# small_pcb_explorator_58mm_lyre_v1_1.net
KiCad netlist of a schematic drawn in EAGLE
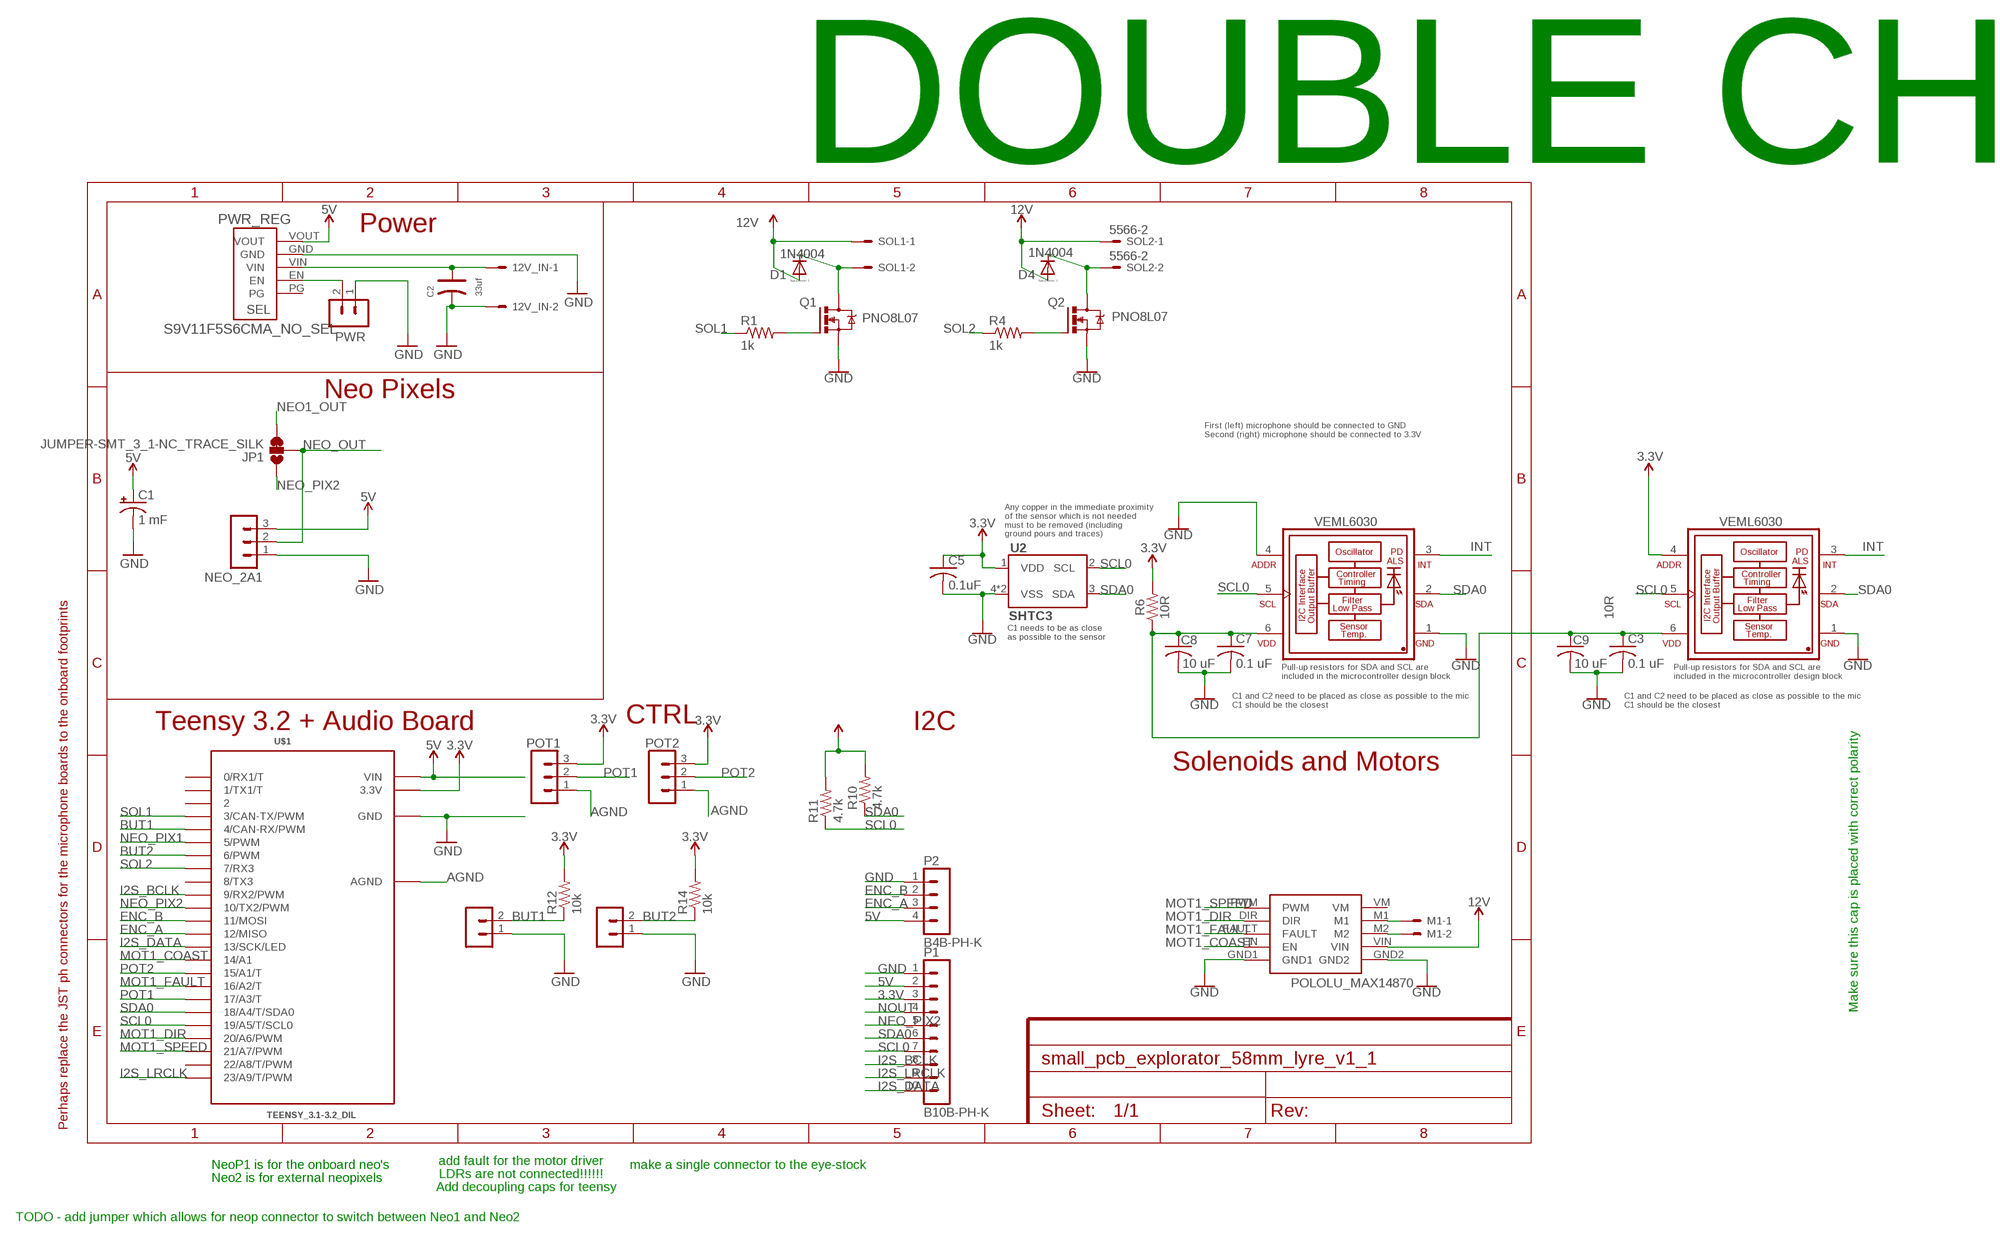
[diagram p0: schematic, sheet 1, part 1 of 2]
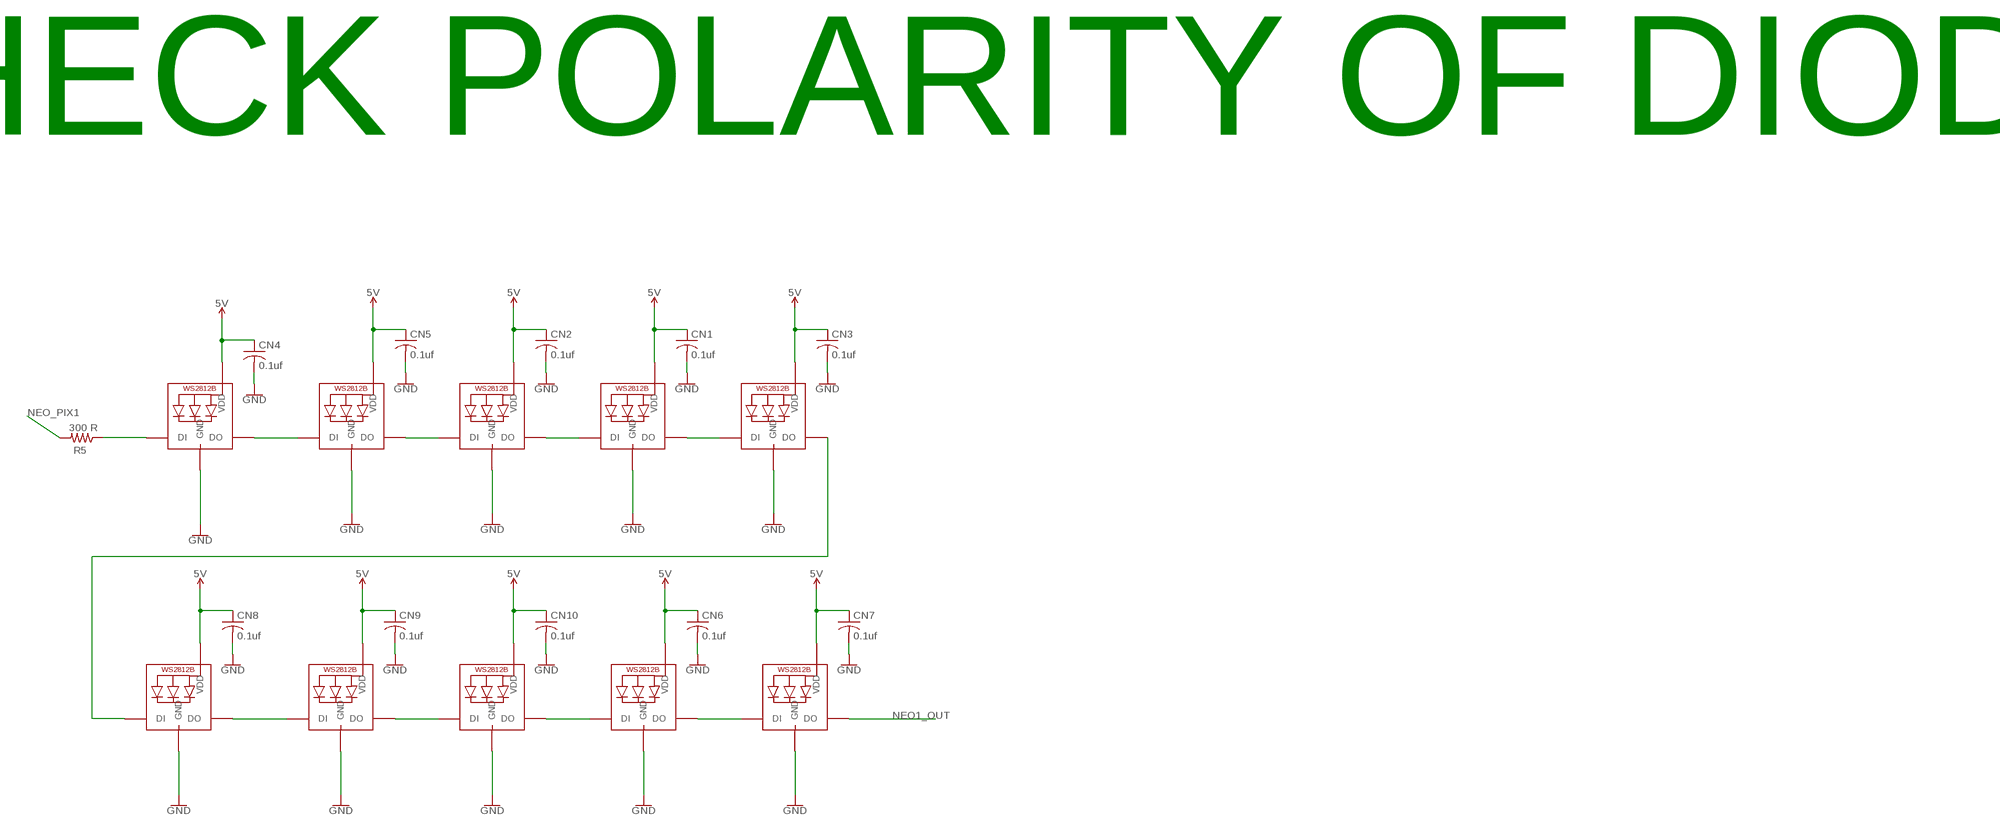
[diagram p1: schematic, sheet 1, part 2 of 2]

(export (version "E")
  (design (tool "Eeschema 10.0.6"))
  (components
    (comp (ref "12V_IN")
      (value "5566-2")
      (footprint "eagle-import:5566-2")
      (fields (field (name "MF") "MOLEX"))
      (libsource (lib "eagle-import") (part "5566-2"))
    )
    (comp (ref "BUT1")
      (value "B2B-PH-K")
      (footprint "eagle-import:B2B-PH-K")
      (libsource (lib "eagle-import") (part "B2B-PH-K"))
    )
    (comp (ref "BUT2")
      (value "B2B-PH-K")
      (footprint "eagle-import:B2B-PH-K")
      (libsource (lib "eagle-import") (part "B2B-PH-K"))
    )
    (comp (ref "C1")
      (value "1 mF")
      (footprint "eagle-import:UD-10X10_NICHICON")
      (libsource (lib "eagle-import") (part "CPOL-USUD-10X10"))
    )
    (comp (ref "C2")
      (value "33uf")
      (footprint "eagle-import:PC-D5.3MM")
      (fields (field (name "MPN") "KS 100uF/16V"))
      (libsource (lib "eagle-import") (part "DIP-ALUMINUM-47UF-16V(D5-H7MM)"))
    )
    (comp (ref "C3")
      (value "0.1 uF")
      (footprint "eagle-import:C0805")
      (libsource (lib "eagle-import") (part "C-USC0805"))
    )
    (comp (ref "C5")
      (value "0.1uF")
      (footprint "eagle-import:C0805")
      (libsource (lib "eagle-import") (part "C-USC0805"))
    )
    (comp (ref "C7")
      (value "0.1 uF")
      (footprint "eagle-import:C0805")
      (libsource (lib "eagle-import") (part "C-USC0805"))
    )
    (comp (ref "C8")
      (value "10 uF")
      (footprint "eagle-import:C0805")
      (libsource (lib "eagle-import") (part "C-USC0805"))
    )
    (comp (ref "C9")
      (value "10 uF")
      (footprint "eagle-import:C0805")
      (libsource (lib "eagle-import") (part "C-USC0805"))
    )
    (comp (ref "CN1")
      (value "0.1uf")
      (footprint "eagle-import:C0805K")
      (libsource (lib "eagle-import") (part "resistor_348_C-USC0805K"))
    )
    (comp (ref "CN2")
      (value "0.1uf")
      (footprint "eagle-import:C0805K")
      (libsource (lib "eagle-import") (part "resistor_348_C-USC0805K"))
    )
    (comp (ref "CN3")
      (value "0.1uf")
      (footprint "eagle-import:C0805K")
      (libsource (lib "eagle-import") (part "resistor_348_C-USC0805K"))
    )
    (comp (ref "CN4")
      (value "0.1uf")
      (footprint "eagle-import:C0805K")
      (libsource (lib "eagle-import") (part "resistor_348_C-USC0805K"))
    )
    (comp (ref "CN5")
      (value "0.1uf")
      (footprint "eagle-import:C0805K")
      (libsource (lib "eagle-import") (part "resistor_348_C-USC0805K"))
    )
    (comp (ref "CN6")
      (value "0.1uf")
      (footprint "eagle-import:C0805K")
      (libsource (lib "eagle-import") (part "resistor_348_C-USC0805K"))
    )
    (comp (ref "CN7")
      (value "0.1uf")
      (footprint "eagle-import:C0805K")
      (libsource (lib "eagle-import") (part "resistor_348_C-USC0805K"))
    )
    (comp (ref "CN8")
      (value "0.1uf")
      (footprint "eagle-import:C0805K")
      (libsource (lib "eagle-import") (part "resistor_348_C-USC0805K"))
    )
    (comp (ref "CN9")
      (value "0.1uf")
      (footprint "eagle-import:C0805K")
      (libsource (lib "eagle-import") (part "resistor_348_C-USC0805K"))
    )
    (comp (ref "CN10")
      (value "0.1uf")
      (footprint "eagle-import:C0805K")
      (libsource (lib "eagle-import") (part "resistor_348_C-USC0805K"))
    )
    (comp (ref "D1")
      (value "1N4004")
      (footprint "eagle-import:DIODE_DO35-7")
      (libsource (lib "eagle-import") (part "DIODE_E-DO35-7"))
    )
    (comp (ref "D4")
      (value "1N4004")
      (footprint "eagle-import:DIODE_DO35-7")
      (libsource (lib "eagle-import") (part "DIODE_E-DO35-7"))
    )
    (comp (ref "JP1")
      (value "JUMPER-SMT_3_1-NC_TRACE_SILK")
      (footprint "eagle-import:SMT-JUMPER_3_1-NC_TRACE_SILK")
      (libsource (lib "eagle-import") (part "JUMPER-SMT_3_1-NC_TRACE_SILK"))
    )
    (comp (ref "M1")
      (value "5566-2")
      (footprint "eagle-import:5566-2")
      (fields (field (name "MF") "MOLEX"))
      (libsource (lib "eagle-import") (part "5566-2"))
    )
    (comp (ref "MOT1")
      (value "POLOLU_MAX14870")
      (footprint "eagle-import:POLOLU_MAX14870")
      (libsource (lib "eagle-import") (part "POLOLU_MAX14870"))
    )
    (comp (ref "NEO1")
      (value "WS2812B5050")
      (footprint "eagle-import:WS2812B")
      (libsource (lib "eagle-import") (part "WS2812B5050"))
    )
    (comp (ref "NEO2")
      (value "WS2812B5050")
      (footprint "eagle-import:WS2812B")
      (libsource (lib "eagle-import") (part "WS2812B5050"))
    )
    (comp (ref "NEO3")
      (value "WS2812B5050")
      (footprint "eagle-import:WS2812B")
      (libsource (lib "eagle-import") (part "WS2812B5050"))
    )
    (comp (ref "NEO4")
      (value "WS2812B5050")
      (footprint "eagle-import:WS2812B")
      (libsource (lib "eagle-import") (part "WS2812B5050"))
    )
    (comp (ref "NEO5")
      (value "WS2812B5050")
      (footprint "eagle-import:WS2812B")
      (libsource (lib "eagle-import") (part "WS2812B5050"))
    )
    (comp (ref "NEO6")
      (value "WS2812B5050")
      (footprint "eagle-import:WS2812B")
      (libsource (lib "eagle-import") (part "WS2812B5050"))
    )
    (comp (ref "NEO7")
      (value "WS2812B5050")
      (footprint "eagle-import:WS2812B")
      (libsource (lib "eagle-import") (part "WS2812B5050"))
    )
    (comp (ref "NEO8")
      (value "WS2812B5050")
      (footprint "eagle-import:WS2812B")
      (libsource (lib "eagle-import") (part "WS2812B5050"))
    )
    (comp (ref "NEO9")
      (value "WS2812B5050")
      (footprint "eagle-import:WS2812B")
      (libsource (lib "eagle-import") (part "WS2812B5050"))
    )
    (comp (ref "NEO10")
      (value "WS2812B5050")
      (footprint "eagle-import:WS2812B")
      (libsource (lib "eagle-import") (part "WS2812B5050"))
    )
    (comp (ref "NEO_2A1")
      (value "B3B-PH-K")
      (footprint "eagle-import:B3B-PH-K")
      (libsource (lib "eagle-import") (part "B3B-PH-K"))
    )
    (comp (ref "P1")
      (value "B10B-PH-K")
      (footprint "eagle-import:B10B-PH-K")
      (libsource (lib "eagle-import") (part "B10B-PH-K"))
    )
    (comp (ref "P2")
      (value "B4B-PH-K")
      (footprint "eagle-import:B4B-PH-K")
      (libsource (lib "eagle-import") (part "B4B-PH-K"))
    )
    (comp (ref "POT1")
      (value "B3B-PH-K")
      (footprint "eagle-import:B3B-PH-K")
      (libsource (lib "eagle-import") (part "B3B-PH-K"))
    )
    (comp (ref "POT2")
      (value "B3B-PH-K")
      (footprint "eagle-import:B3B-PH-K")
      (libsource (lib "eagle-import") (part "B3B-PH-K"))
    )
    (comp (ref "PWR")
      (value "B2B-PH-K")
      (footprint "eagle-import:B2B-PH-K")
      (libsource (lib "eagle-import") (part "B2B-PH-K"))
    )
    (comp (ref "PWR_REG")
      (value "S9V11F5S6CMA_NO_SEL")
      (footprint "eagle-import:S9V11F3S5CMA_NO_SEL")
      (libsource (lib "eagle-import") (part "S9V11F5S6CMA_NO_SEL"))
    )
    (comp (ref "Q1")
      (value "PNO8L07")
      (footprint "eagle-import:TO220BV")
      (libsource (lib "eagle-import") (part "IRF540"))
    )
    (comp (ref "Q2")
      (value "PNO8L07")
      (footprint "eagle-import:TO220BV")
      (libsource (lib "eagle-import") (part "IRF540"))
    )
    (comp (ref "R1")
      (value "1k")
      (footprint "eagle-import:R0805")
      (libsource (lib "eagle-import") (part "rcl_334_R-US_R0805"))
    )
    (comp (ref "R4")
      (value "1k")
      (footprint "eagle-import:R0805")
      (libsource (lib "eagle-import") (part "rcl_334_R-US_R0805"))
    )
    (comp (ref "R5")
      (value "300 R")
      (footprint "eagle-import:R0805")
      (libsource (lib "eagle-import") (part "R-US_R0805"))
    )
    (comp (ref "R6")
      (value "10 R")
      (footprint "eagle-import:R0805")
      (libsource (lib "eagle-import") (part "R-US_R0805"))
    )
    (comp (ref "R10")
      (value "4.7k")
      (footprint "eagle-import:R0805")
      (libsource (lib "eagle-import") (part "rcl_334_R-US_R0805"))
    )
    (comp (ref "R11")
      (value "4.7k")
      (footprint "eagle-import:R0805")
      (libsource (lib "eagle-import") (part "rcl_334_R-US_R0805"))
    )
    (comp (ref "R12")
      (value "10k")
      (footprint "eagle-import:R0805")
      (libsource (lib "eagle-import") (part "rcl_334_R-US_R0805"))
    )
    (comp (ref "R14")
      (value "10k")
      (footprint "eagle-import:R0805")
      (libsource (lib "eagle-import") (part "rcl_334_R-US_R0805"))
    )
    (comp (ref "SOL1")
      (value "5566-2")
      (footprint "eagle-import:5566-2")
      (fields (field (name "MF") "MOLEX"))
      (libsource (lib "eagle-import") (part "5566-2"))
    )
    (comp (ref "SOL2")
      (value "5566-2")
      (footprint "eagle-import:5566-2")
      (fields (field (name "MF") "MOLEX"))
      (libsource (lib "eagle-import") (part "5566-2"))
    )
    (comp (ref "U$1")
      (value "TEENSY_3.1-3.2_DIL")
      (footprint "eagle-import:TEENSY_3.0-3.2&LC_DIL")
      (libsource (lib "eagle-import") (part "TEENSY_3.1-3.2_DIL"))
    )
    (comp (ref "U2")
      (value "SHTC3")
      (footprint "eagle-import:SHTC3")
      (libsource (lib "eagle-import") (part "SHTC3"))
    )
    (comp (ref "VMEL1")
      (value "VEML6030")
      (footprint "eagle-import:VISHAY_VEML6030_2X2X0.87")
      (fields (field (name "MF") "Vishay Semiconductor") (field (name "MP") "VEML6030-GS15"))
      (libsource (lib "eagle-import") (part "VEML6030-GS15"))
    )
    (comp (ref "VMEL2")
      (value "VEML6030")
      (footprint "eagle-import:VISHAY_VEML6030_2X2X0.87")
      (fields (field (name "MF") "Vishay Semiconductor") (field (name "MP") "VEML6030-GS15"))
      (libsource (lib "eagle-import") (part "VEML6030-GS15"))
    )
  )
  (nets
    (net (code "1") (name "/AGND") (class "Default")
      (node (ref "POT1") (pin "1") (pinfunction "1_1") (pintype "passive"))
      (node (ref "POT2") (pin "1") (pinfunction "1_1") (pintype "passive"))
      (node (ref "U$1") (pin "AGND") (pinfunction "AGND_AGND") (pintype "power_in"))
    )
    (net (code "2") (name "/BUT1") (class "Default")
      (node (ref "BUT1") (pin "2") (pinfunction "2_2") (pintype "passive"))
      (node (ref "R12") (pin "1") (pinfunction "1_1") (pintype "passive"))
      (node (ref "U$1") (pin "4") (pinfunction "4/CAN-RX/PWM_4") (pintype "bidirectional"))
    )
    (net (code "3") (name "/BUT2") (class "Default")
      (node (ref "BUT2") (pin "2") (pinfunction "2_2") (pintype "passive"))
      (node (ref "R14") (pin "1") (pinfunction "1_1") (pintype "passive"))
      (node (ref "U$1") (pin "6") (pinfunction "6/PWM_6") (pintype "bidirectional"))
    )
    (net (code "4") (name "/ENC_A") (class "Default")
      (node (ref "P2") (pin "3") (pinfunction "3_3") (pintype "passive"))
      (node (ref "U$1") (pin "12") (pinfunction "12/MISO_12") (pintype "bidirectional"))
    )
    (net (code "5") (name "/ENC_B") (class "Default")
      (node (ref "P2") (pin "2") (pinfunction "2_2") (pintype "passive"))
      (node (ref "U$1") (pin "11") (pinfunction "11/MOSI_11") (pintype "bidirectional"))
    )
    (net (code "6") (name "/I2S_BCLK") (class "Default")
      (node (ref "P1") (pin "8") (pinfunction "8_8") (pintype "passive"))
      (node (ref "U$1") (pin "9") (pinfunction "9/RX2/PWM_9") (pintype "bidirectional"))
    )
    (net (code "7") (name "/I2S_DATA") (class "Default")
      (node (ref "P1") (pin "10") (pinfunction "10_10") (pintype "passive"))
      (node (ref "U$1") (pin "13") (pinfunction "13/SCK/LED_13") (pintype "bidirectional"))
    )
    (net (code "8") (name "/I2S_LRCLK") (class "Default")
      (node (ref "P1") (pin "9") (pinfunction "9_9") (pintype "passive"))
      (node (ref "U$1") (pin "23/A9") (pinfunction "23/A9/T/PWM_23/A9") (pintype "bidirectional"))
    )
    (net (code "9") (name "/INT") (class "Default")
      (node (ref "VMEL1") (pin "3") (pinfunction "INT_3") (pintype "output"))
      (node (ref "VMEL2") (pin "3") (pinfunction "INT_3") (pintype "output"))
    )
    (net (code "10") (name "/MOT1_COAST") (class "Default")
      (node (ref "MOT1") (pin "EN") (pinfunction "EN_EN") (pintype "bidirectional"))
      (node (ref "U$1") (pin "14/A0") (pinfunction "14/A1_14/A0") (pintype "bidirectional"))
    )
    (net (code "11") (name "/MOT1_DIR") (class "Default")
      (node (ref "MOT1") (pin "DIR") (pinfunction "DIR_DIR") (pintype "bidirectional"))
      (node (ref "U$1") (pin "20/A6") (pinfunction "20/A6/PWM_20/A6") (pintype "bidirectional"))
    )
    (net (code "12") (name "/MOT1_FAULT") (class "Default")
      (node (ref "MOT1") (pin "FAULT") (pinfunction "FAULT_FAULT") (pintype "bidirectional"))
      (node (ref "U$1") (pin "16/A2") (pinfunction "16/A2/T_16/A2") (pintype "bidirectional"))
    )
    (net (code "13") (name "/MOT1_SPEED") (class "Default")
      (node (ref "MOT1") (pin "PWM") (pinfunction "PWM_PWM") (pintype "bidirectional"))
      (node (ref "U$1") (pin "21/A7") (pinfunction "21/A7/PWM_21/A7") (pintype "bidirectional"))
    )
    (net (code "14") (name "/NEO1_OUT") (class "Default")
      (node (ref "JP1") (pin "3") (pinfunction "3_3") (pintype "passive"))
      (node (ref "NEO7") (pin "2-DOUT") (pinfunction "DO_2-DOUT") (pintype "output"))
    )
    (net (code "15") (name "/NEO_OUT") (class "Default")
      (node (ref "JP1") (pin "2") (pinfunction "2_2") (pintype "passive"))
      (node (ref "NEO_2A1") (pin "2") (pinfunction "2_2") (pintype "passive"))
    )
    (net (code "16") (name "/NEO_PIX1") (class "Default")
      (node (ref "R5") (pin "2") (pinfunction "2_2") (pintype "passive"))
      (node (ref "U$1") (pin "5") (pinfunction "5/PWM_5") (pintype "bidirectional"))
    )
    (net (code "17") (name "/NEO_PIX2") (class "Default")
      (node (ref "JP1") (pin "1") (pinfunction "1_1") (pintype "passive"))
      (node (ref "P1") (pin "5") (pinfunction "5_5") (pintype "passive"))
      (node (ref "U$1") (pin "10") (pinfunction "10/TX2/PWM_10") (pintype "bidirectional"))
    )
    (net (code "18") (name "/NOUT") (class "Default")
      (node (ref "P1") (pin "4") (pinfunction "4_4") (pintype "passive"))
    )
    (net (code "19") (name "/POT1") (class "Default")
      (node (ref "POT1") (pin "2") (pinfunction "2_2") (pintype "passive"))
      (node (ref "U$1") (pin "17/A3") (pinfunction "17/A3/T_17/A3") (pintype "bidirectional"))
    )
    (net (code "20") (name "/POT2") (class "Default")
      (node (ref "POT2") (pin "2") (pinfunction "2_2") (pintype "passive"))
      (node (ref "U$1") (pin "15/A1") (pinfunction "15/A1/T_15/A1") (pintype "bidirectional"))
    )
    (net (code "21") (name "/SCL0") (class "Default")
      (node (ref "P1") (pin "7") (pinfunction "7_7") (pintype "passive"))
      (node (ref "R11") (pin "1") (pinfunction "1_1") (pintype "passive"))
      (node (ref "U$1") (pin "19/A5") (pinfunction "19/A5/T/SCL0_19/A5") (pintype "bidirectional"))
      (node (ref "U2") (pin "2") (pinfunction "SCL_2") (pintype "bidirectional"))
      (node (ref "VMEL1") (pin "5") (pinfunction "SCL_5") (pintype "input"))
      (node (ref "VMEL2") (pin "5") (pinfunction "SCL_5") (pintype "input"))
    )
    (net (code "22") (name "/SDA0") (class "Default")
      (node (ref "P1") (pin "6") (pinfunction "6_6") (pintype "passive"))
      (node (ref "R10") (pin "1") (pinfunction "1_1") (pintype "passive"))
      (node (ref "U$1") (pin "18/A4") (pinfunction "18/A4/T/SDA0_18/A4") (pintype "bidirectional"))
      (node (ref "U2") (pin "3") (pinfunction "SDA_3") (pintype "bidirectional"))
      (node (ref "VMEL1") (pin "2") (pinfunction "SDA_2") (pintype "bidirectional"))
      (node (ref "VMEL2") (pin "2") (pinfunction "SDA_2") (pintype "bidirectional"))
    )
    (net (code "23") (name "/SOL1") (class "Default")
      (node (ref "R1") (pin "1") (pinfunction "1_1") (pintype "passive"))
      (node (ref "U$1") (pin "3") (pinfunction "3/CAN-TX/PWM_3") (pintype "bidirectional"))
    )
    (net (code "24") (name "/SOL2") (class "Default")
      (node (ref "R4") (pin "1") (pinfunction "1_1") (pintype "passive"))
      (node (ref "U$1") (pin "7") (pinfunction "7/RX3_7") (pintype "bidirectional"))
    )
    (net (code "25") (name "3.3V") (class "Default")
      (node (ref "C5") (pin "1") (pinfunction "1_1") (pintype "passive"))
      (node (ref "P1") (pin "3") (pinfunction "3_3") (pintype "passive"))
      (node (ref "POT1") (pin "3") (pinfunction "3_3") (pintype "passive"))
      (node (ref "POT2") (pin "3") (pinfunction "3_3") (pintype "passive"))
      (node (ref "R10") (pin "2") (pinfunction "2_2") (pintype "passive"))
      (node (ref "R11") (pin "2") (pinfunction "2_2") (pintype "passive"))
      (node (ref "R12") (pin "2") (pinfunction "2_2") (pintype "passive"))
      (node (ref "R14") (pin "2") (pinfunction "2_2") (pintype "passive"))
      (node (ref "R6") (pin "2") (pinfunction "2_2") (pintype "passive"))
      (node (ref "U$1") (pin "3.3V") (pinfunction "3.3V_3.3V") (pintype "power_in"))
      (node (ref "U2") (pin "1") (pinfunction "VDD_1") (pintype "bidirectional"))
      (node (ref "VMEL2") (pin "4") (pinfunction "ADDR_4") (pintype "bidirectional"))
    )
    (net (code "26") (name "5V") (class "Default")
      (node (ref "C1") (pin "+") (pinfunction "+_+") (pintype "passive"))
      (node (ref "CN1") (pin "1") (pinfunction "1_1") (pintype "passive"))
      (node (ref "CN10") (pin "1") (pinfunction "1_1") (pintype "passive"))
      (node (ref "CN2") (pin "1") (pinfunction "1_1") (pintype "passive"))
      (node (ref "CN3") (pin "1") (pinfunction "1_1") (pintype "passive"))
      (node (ref "CN4") (pin "1") (pinfunction "1_1") (pintype "passive"))
      (node (ref "CN5") (pin "1") (pinfunction "1_1") (pintype "passive"))
      (node (ref "CN6") (pin "1") (pinfunction "1_1") (pintype "passive"))
      (node (ref "CN7") (pin "1") (pinfunction "1_1") (pintype "passive"))
      (node (ref "CN8") (pin "1") (pinfunction "1_1") (pintype "passive"))
      (node (ref "CN9") (pin "1") (pinfunction "1_1") (pintype "passive"))
      (node (ref "NEO1") (pin "1-VDD") (pinfunction "VDD_1-VDD") (pintype "power_in"))
      (node (ref "NEO10") (pin "1-VDD") (pinfunction "VDD_1-VDD") (pintype "power_in"))
      (node (ref "NEO2") (pin "1-VDD") (pinfunction "VDD_1-VDD") (pintype "power_in"))
      (node (ref "NEO3") (pin "1-VDD") (pinfunction "VDD_1-VDD") (pintype "power_in"))
      (node (ref "NEO4") (pin "1-VDD") (pinfunction "VDD_1-VDD") (pintype "power_in"))
      (node (ref "NEO5") (pin "1-VDD") (pinfunction "VDD_1-VDD") (pintype "power_in"))
      (node (ref "NEO6") (pin "1-VDD") (pinfunction "VDD_1-VDD") (pintype "power_in"))
      (node (ref "NEO7") (pin "1-VDD") (pinfunction "VDD_1-VDD") (pintype "power_in"))
      (node (ref "NEO8") (pin "1-VDD") (pinfunction "VDD_1-VDD") (pintype "power_in"))
      (node (ref "NEO9") (pin "1-VDD") (pinfunction "VDD_1-VDD") (pintype "power_in"))
      (node (ref "NEO_2A1") (pin "3") (pinfunction "3_3") (pintype "passive"))
      (node (ref "P1") (pin "2") (pinfunction "2_2") (pintype "passive"))
      (node (ref "P2") (pin "4") (pinfunction "4_4") (pintype "passive"))
      (node (ref "PWR_REG") (pin "VOUT") (pinfunction "VOUT_VOUT") (pintype "bidirectional"))
      (node (ref "U$1") (pin "VIN") (pinfunction "VIN_VIN") (pintype "power_in"))
    )
    (net (code "27") (name "12V") (class "Default")
      (node (ref "12V_IN") (pin "1") (pinfunction "S_1") (pintype "passive"))
      (node (ref "C2") (pin "+") (pinfunction "+_+") (pintype "passive"))
      (node (ref "D1") (pin "A") (pinfunction "C_A") (pintype "passive"))
      (node (ref "D4") (pin "A") (pinfunction "C_A") (pintype "passive"))
      (node (ref "MOT1") (pin "VIN") (pinfunction "VIN_VIN") (pintype "bidirectional"))
      (node (ref "PWR_REG") (pin "VIN") (pinfunction "VIN_VIN") (pintype "bidirectional"))
      (node (ref "SOL1") (pin "1") (pinfunction "S_1") (pintype "passive"))
      (node (ref "SOL2") (pin "1") (pinfunction "S_1") (pintype "passive"))
    )
    (net (code "28") (name "GND") (class "Default")
      (node (ref "12V_IN") (pin "2") (pinfunction "S_2") (pintype "passive"))
      (node (ref "BUT1") (pin "1") (pinfunction "1_1") (pintype "passive"))
      (node (ref "BUT2") (pin "1") (pinfunction "1_1") (pintype "passive"))
      (node (ref "C1") (pin "-") (pinfunction "-_-") (pintype "passive"))
      (node (ref "C2") (pin "-") (pinfunction "-_-") (pintype "passive"))
      (node (ref "C3") (pin "2") (pinfunction "2_2") (pintype "passive"))
      (node (ref "C5") (pin "2") (pinfunction "2_2") (pintype "passive"))
      (node (ref "C7") (pin "2") (pinfunction "2_2") (pintype "passive"))
      (node (ref "C8") (pin "2") (pinfunction "2_2") (pintype "passive"))
      (node (ref "C9") (pin "2") (pinfunction "2_2") (pintype "passive"))
      (node (ref "CN1") (pin "2") (pinfunction "2_2") (pintype "passive"))
      (node (ref "CN10") (pin "2") (pinfunction "2_2") (pintype "passive"))
      (node (ref "CN2") (pin "2") (pinfunction "2_2") (pintype "passive"))
      (node (ref "CN3") (pin "2") (pinfunction "2_2") (pintype "passive"))
      (node (ref "CN4") (pin "2") (pinfunction "2_2") (pintype "passive"))
      (node (ref "CN5") (pin "2") (pinfunction "2_2") (pintype "passive"))
      (node (ref "CN6") (pin "2") (pinfunction "2_2") (pintype "passive"))
      (node (ref "CN7") (pin "2") (pinfunction "2_2") (pintype "passive"))
      (node (ref "CN8") (pin "2") (pinfunction "2_2") (pintype "passive"))
      (node (ref "CN9") (pin "2") (pinfunction "2_2") (pintype "passive"))
      (node (ref "MOT1") (pin "GND1") (pinfunction "GND1_GND1") (pintype "bidirectional"))
      (node (ref "MOT1") (pin "GND2") (pinfunction "GND2_GND2") (pintype "bidirectional"))
      (node (ref "NEO1") (pin "3-GND") (pinfunction "GND_3-GND") (pintype "power_in"))
      (node (ref "NEO10") (pin "3-GND") (pinfunction "GND_3-GND") (pintype "power_in"))
      (node (ref "NEO2") (pin "3-GND") (pinfunction "GND_3-GND") (pintype "power_in"))
      (node (ref "NEO3") (pin "3-GND") (pinfunction "GND_3-GND") (pintype "power_in"))
      (node (ref "NEO4") (pin "3-GND") (pinfunction "GND_3-GND") (pintype "power_in"))
      (node (ref "NEO5") (pin "3-GND") (pinfunction "GND_3-GND") (pintype "power_in"))
      (node (ref "NEO6") (pin "3-GND") (pinfunction "GND_3-GND") (pintype "power_in"))
      (node (ref "NEO7") (pin "3-GND") (pinfunction "GND_3-GND") (pintype "power_in"))
      (node (ref "NEO8") (pin "3-GND") (pinfunction "GND_3-GND") (pintype "power_in"))
      (node (ref "NEO9") (pin "3-GND") (pinfunction "GND_3-GND") (pintype "power_in"))
      (node (ref "NEO_2A1") (pin "1") (pinfunction "1_1") (pintype "passive"))
      (node (ref "P1") (pin "1") (pinfunction "1_1") (pintype "passive"))
      (node (ref "P2") (pin "1") (pinfunction "1_1") (pintype "passive"))
      (node (ref "PWR") (pin "1") (pinfunction "1_1") (pintype "passive"))
      (node (ref "PWR_REG") (pin "GND") (pinfunction "GND_GND") (pintype "bidirectional"))
      (node (ref "Q1") (pin "S") (pinfunction "S_S") (pintype "passive"))
      (node (ref "Q2") (pin "S") (pinfunction "S_S") (pintype "passive"))
      (node (ref "U$1") (pin "GND") (pinfunction "GND_GND") (pintype "power_in"))
      (node (ref "U2") (pin "4") (pinfunction "VSS_4") (pintype "bidirectional"))
      (node (ref "U2") (pin "5") (pinfunction "VSS_5") (pintype "bidirectional"))
      (node (ref "VMEL1") (pin "1") (pinfunction "GND_1") (pintype "power_in"))
      (node (ref "VMEL1") (pin "4") (pinfunction "ADDR_4") (pintype "bidirectional"))
      (node (ref "VMEL2") (pin "1") (pinfunction "GND_1") (pintype "power_in"))
    )
    (net (code "29") (name "Net-(D1-A)") (class "Default")
      (node (ref "D1") (pin "C") (pinfunction "A_C") (pintype "passive"))
      (node (ref "Q1") (pin "D") (pinfunction "D_D") (pintype "passive"))
      (node (ref "SOL1") (pin "2") (pinfunction "S_2") (pintype "passive"))
    )
    (net (code "30") (name "Net-(D4-A)") (class "Default")
      (node (ref "D4") (pin "C") (pinfunction "A_C") (pintype "passive"))
      (node (ref "Q2") (pin "D") (pinfunction "D_D") (pintype "passive"))
      (node (ref "SOL2") (pin "2") (pinfunction "S_2") (pintype "passive"))
    )
    (net (code "31") (name "Net-(M1A-S)") (class "Default")
      (node (ref "M1") (pin "1") (pinfunction "S_1") (pintype "passive"))
      (node (ref "MOT1") (pin "M1") (pinfunction "M1_M1") (pintype "bidirectional"))
    )
    (net (code "32") (name "Net-(M1B-S)") (class "Default")
      (node (ref "M1") (pin "2") (pinfunction "S_2") (pintype "passive"))
      (node (ref "MOT1") (pin "M2") (pinfunction "M2_M2") (pintype "bidirectional"))
    )
    (net (code "33") (name "Net-(NEO1-DI)") (class "Default")
      (node (ref "NEO1") (pin "4-DIN") (pinfunction "DI_4-DIN") (pintype "input"))
      (node (ref "NEO5") (pin "2-DOUT") (pinfunction "DO_2-DOUT") (pintype "output"))
    )
    (net (code "34") (name "Net-(NEO1-DO)") (class "Default")
      (node (ref "NEO1") (pin "2-DOUT") (pinfunction "DO_2-DOUT") (pintype "output"))
      (node (ref "NEO2") (pin "4-DIN") (pinfunction "DI_4-DIN") (pintype "input"))
    )
    (net (code "35") (name "Net-(NEO2-DO)") (class "Default")
      (node (ref "NEO2") (pin "2-DOUT") (pinfunction "DO_2-DOUT") (pintype "output"))
      (node (ref "NEO3") (pin "4-DIN") (pinfunction "DI_4-DIN") (pintype "input"))
    )
    (net (code "36") (name "Net-(NEO3-DO)") (class "Default")
      (node (ref "NEO3") (pin "2-DOUT") (pinfunction "DO_2-DOUT") (pintype "output"))
      (node (ref "NEO8") (pin "4-DIN") (pinfunction "DI_4-DIN") (pintype "input"))
    )
    (net (code "37") (name "Net-(NEO4-DI)") (class "Default")
      (node (ref "NEO4") (pin "4-DIN") (pinfunction "DI_4-DIN") (pintype "input"))
      (node (ref "R5") (pin "1") (pinfunction "1_1") (pintype "passive"))
    )
    (net (code "38") (name "Net-(NEO4-DO)") (class "Default")
      (node (ref "NEO4") (pin "2-DOUT") (pinfunction "DO_2-DOUT") (pintype "output"))
      (node (ref "NEO5") (pin "4-DIN") (pinfunction "DI_4-DIN") (pintype "input"))
    )
    (net (code "39") (name "Net-(NEO6-DO)") (class "Default")
      (node (ref "NEO6") (pin "2-DOUT") (pinfunction "DO_2-DOUT") (pintype "output"))
      (node (ref "NEO7") (pin "4-DIN") (pinfunction "DI_4-DIN") (pintype "input"))
    )
    (net (code "40") (name "Net-(NEO8-DO)") (class "Default")
      (node (ref "NEO8") (pin "2-DOUT") (pinfunction "DO_2-DOUT") (pintype "output"))
      (node (ref "NEO9") (pin "4-DIN") (pinfunction "DI_4-DIN") (pintype "input"))
    )
    (net (code "41") (name "Net-(NEO10-DI)") (class "Default")
      (node (ref "NEO10") (pin "4-DIN") (pinfunction "DI_4-DIN") (pintype "input"))
      (node (ref "NEO9") (pin "2-DOUT") (pinfunction "DO_2-DOUT") (pintype "output"))
    )
    (net (code "42") (name "Net-(NEO10-DO)") (class "Default")
      (node (ref "NEO10") (pin "2-DOUT") (pinfunction "DO_2-DOUT") (pintype "output"))
      (node (ref "NEO6") (pin "4-DIN") (pinfunction "DI_4-DIN") (pintype "input"))
    )
    (net (code "43") (name "Net-(PWR-Pad2)") (class "Default")
      (node (ref "PWR") (pin "2") (pinfunction "2_2") (pintype "passive"))
      (node (ref "PWR_REG") (pin "EN") (pinfunction "EN_EN") (pintype "bidirectional"))
    )
    (net (code "44") (name "Net-(Q1-PadG)") (class "Default")
      (node (ref "Q1") (pin "G") (pinfunction "G_G") (pintype "passive"))
      (node (ref "R1") (pin "2") (pinfunction "2_2") (pintype "passive"))
    )
    (net (code "45") (name "Net-(Q2-PadG)") (class "Default")
      (node (ref "Q2") (pin "G") (pinfunction "G_G") (pintype "passive"))
      (node (ref "R4") (pin "2") (pinfunction "2_2") (pintype "passive"))
    )
    (net (code "46") (name "Net-(VMEL1-VDD)") (class "Default")
      (node (ref "C3") (pin "1") (pinfunction "1_1") (pintype "passive"))
      (node (ref "C7") (pin "1") (pinfunction "1_1") (pintype "passive"))
      (node (ref "C8") (pin "1") (pinfunction "1_1") (pintype "passive"))
      (node (ref "C9") (pin "1") (pinfunction "1_1") (pintype "passive"))
      (node (ref "R6") (pin "1") (pinfunction "1_1") (pintype "passive"))
      (node (ref "VMEL1") (pin "6") (pinfunction "VDD_6") (pintype "power_in"))
      (node (ref "VMEL2") (pin "6") (pinfunction "VDD_6") (pintype "power_in"))
    )
    (net (code "47") (name "unconnected-(MOT1-PadVM)") (class "Default")
      (node (ref "MOT1") (pin "VM") (pinfunction "VM_VM") (pintype "bidirectional"))
    )
    (net (code "48") (name "unconnected-(PWR_REG-PadPG)") (class "Default")
      (node (ref "PWR_REG") (pin "PG") (pinfunction "PG_PG") (pintype "bidirectional"))
    )
    (net (code "49") (name "unconnected-(U$1-0{slash}RX1{slash}T-Pad0)") (class "Default")
      (node (ref "U$1") (pin "0") (pinfunction "0/RX1/T_0") (pintype "bidirectional"))
    )
    (net (code "50") (name "unconnected-(U$1-1{slash}TX1{slash}T-Pad1)") (class "Default")
      (node (ref "U$1") (pin "1") (pinfunction "1/TX1/T_1") (pintype "bidirectional"))
    )
    (net (code "51") (name "unconnected-(U$1-8{slash}TX3-Pad8)") (class "Default")
      (node (ref "U$1") (pin "8") (pinfunction "8/TX3_8") (pintype "bidirectional"))
    )
    (net (code "52") (name "unconnected-(U$1-22{slash}A8{slash}T{slash}PWM-Pad22{slash}A8)") (class "Default")
      (node (ref "U$1") (pin "22/A8") (pinfunction "22/A8/T/PWM_22/A8") (pintype "bidirectional"))
    )
    (net (code "53") (name "unconnected-(U$1-Pad2)") (class "Default")
      (node (ref "U$1") (pin "2") (pinfunction "2_2") (pintype "bidirectional"))
    )
  )
)
